# SupergunBasic.net
KiCad netlist of a schematic drawn in EAGLE
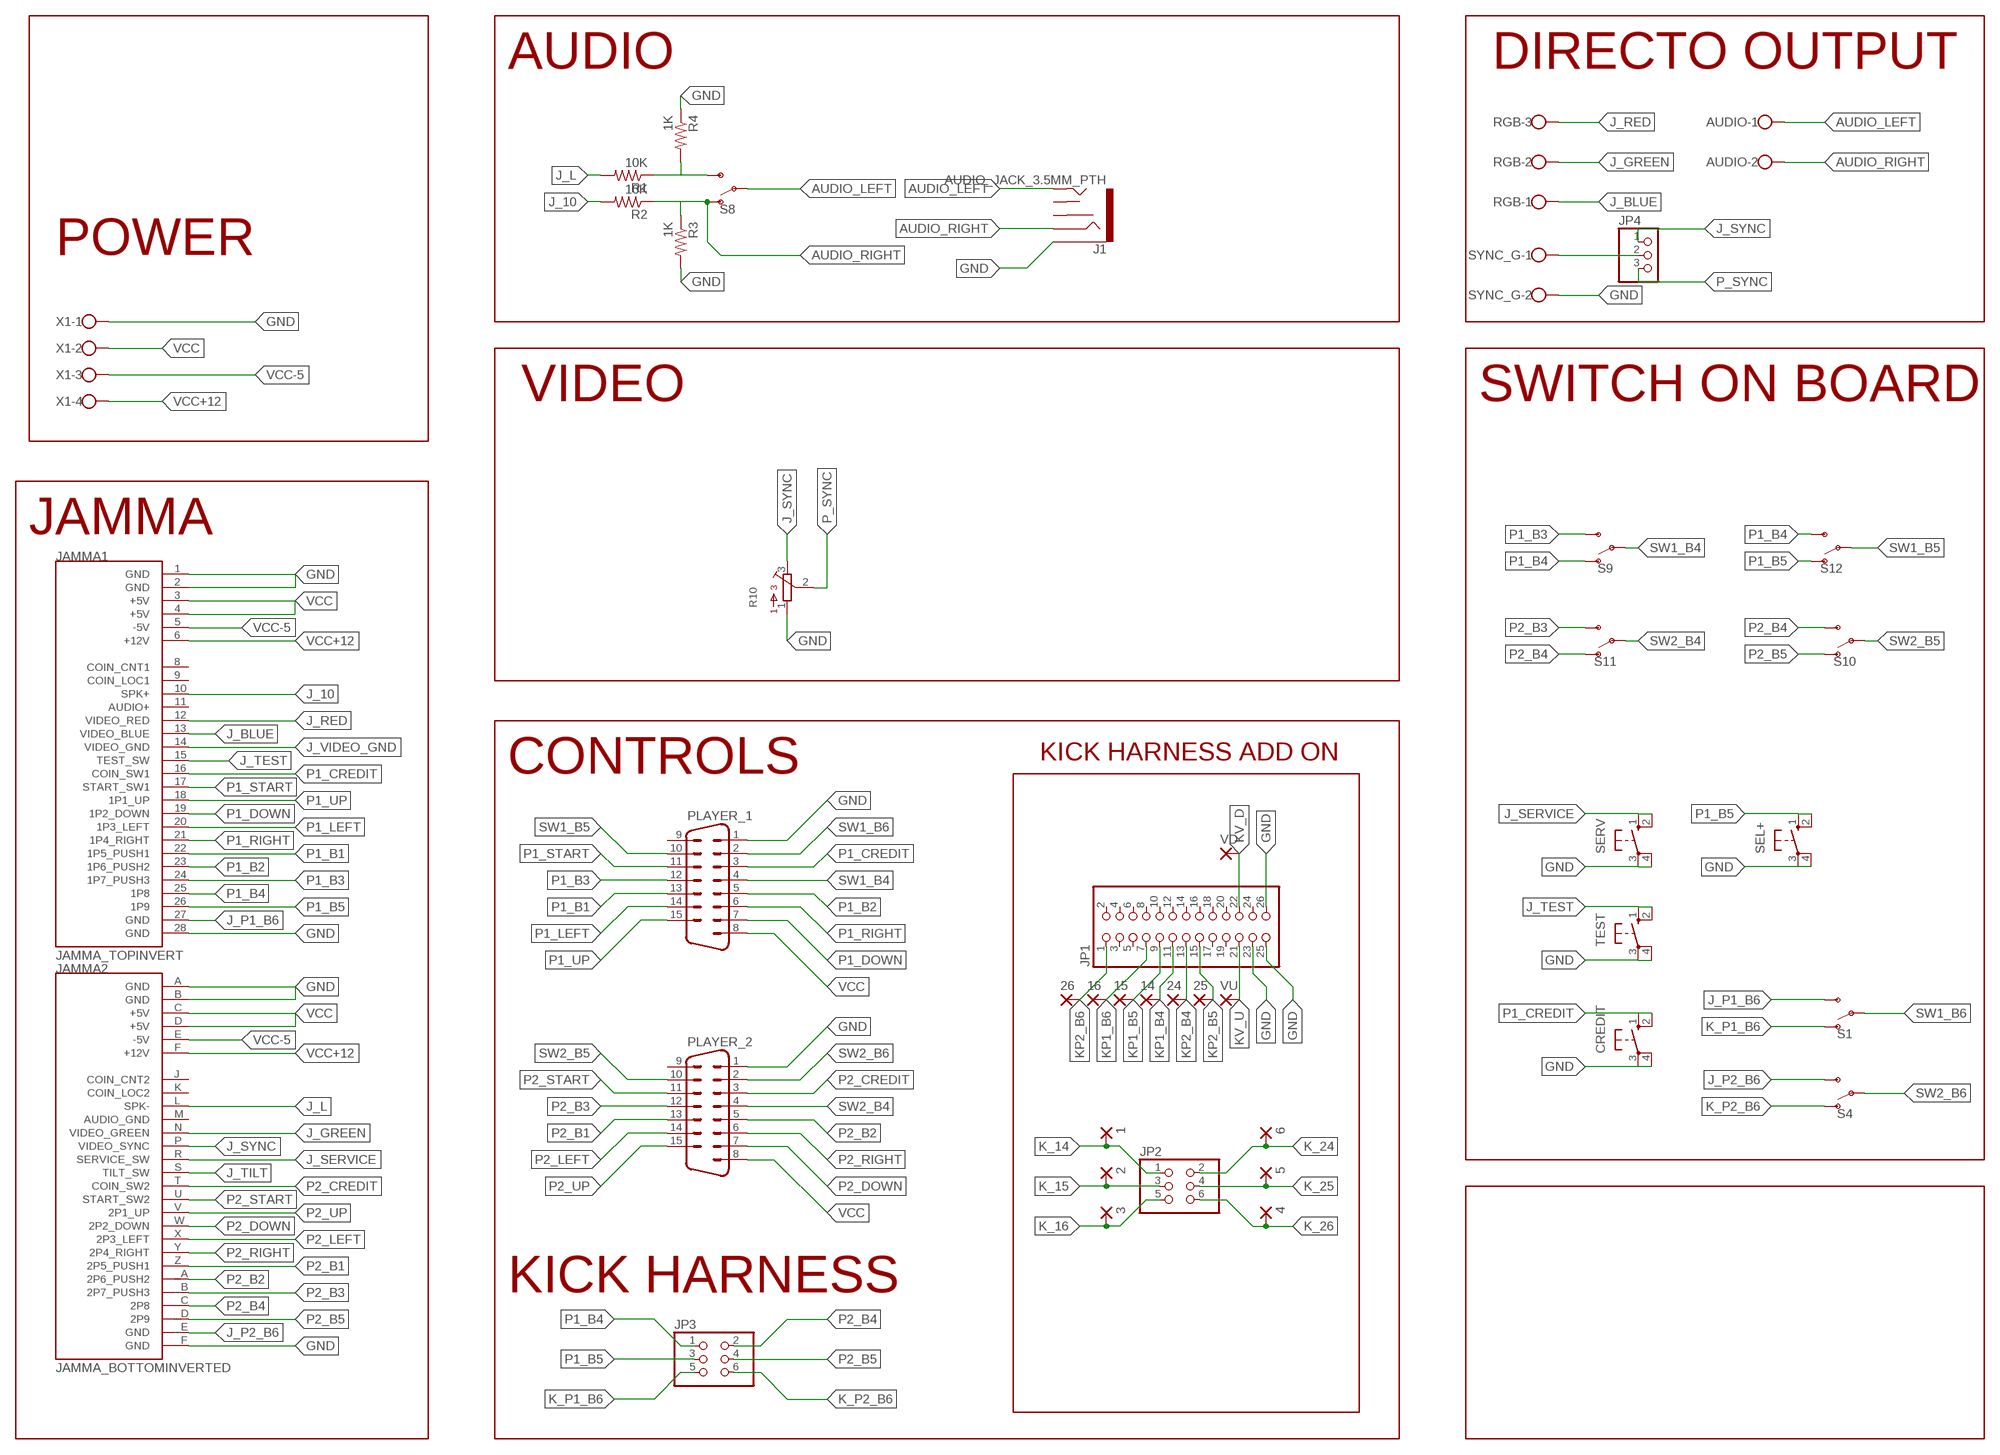
[diagram p0: schematic, sheet 1]

(export (version "E")
  (design (tool "Eeschema 10.0.6"))
  (components
    (comp (ref "1")
      (value "SMD2")
      (footprint "eagle-import:SMD1,27-2,54")
      (libsource (lib "eagle-import") (part "SMD2"))
    )
    (comp (ref "2")
      (value "SMD2")
      (footprint "eagle-import:SMD1,27-2,54")
      (libsource (lib "eagle-import") (part "SMD2"))
    )
    (comp (ref "3")
      (value "SMD2")
      (footprint "eagle-import:SMD1,27-2,54")
      (libsource (lib "eagle-import") (part "SMD2"))
    )
    (comp (ref "4")
      (value "SMD2")
      (footprint "eagle-import:SMD1,27-2,54")
      (libsource (lib "eagle-import") (part "SMD2"))
    )
    (comp (ref "5")
      (value "SMD2")
      (footprint "eagle-import:SMD1,27-2,54")
      (libsource (lib "eagle-import") (part "SMD2"))
    )
    (comp (ref "6")
      (value "SMD2")
      (footprint "eagle-import:SMD1,27-2,54")
      (libsource (lib "eagle-import") (part "SMD2"))
    )
    (comp (ref "14")
      (value "SMD2")
      (footprint "eagle-import:SMD1,27-2,54")
      (libsource (lib "eagle-import") (part "SMD2"))
    )
    (comp (ref "15")
      (value "SMD2")
      (footprint "eagle-import:SMD1,27-2,54")
      (libsource (lib "eagle-import") (part "SMD2"))
    )
    (comp (ref "16")
      (value "SMD2")
      (footprint "eagle-import:SMD1,27-2,54")
      (libsource (lib "eagle-import") (part "SMD2"))
    )
    (comp (ref "24")
      (value "SMD2")
      (footprint "eagle-import:SMD1,27-2,54")
      (libsource (lib "eagle-import") (part "SMD2"))
    )
    (comp (ref "25")
      (value "SMD2")
      (footprint "eagle-import:SMD1,27-2,54")
      (libsource (lib "eagle-import") (part "SMD2"))
    )
    (comp (ref "26")
      (value "SMD2")
      (footprint "eagle-import:SMD1,27-2,54")
      (libsource (lib "eagle-import") (part "SMD2"))
    )
    (comp (ref "AUDIO")
      (value "W237-102")
      (footprint "eagle-import:W237-102")
      (fields (field (name "MPN") "237-102"))
      (libsource (lib "eagle-import") (part "W237-102"))
    )
    (comp (ref "CREDIT")
      (value "10-XX")
      (footprint "eagle-import:B3F-10XX")
      (fields (field (name "MPN") "B3F-1000"))
      (libsource (lib "eagle-import") (part "10-XX"))
    )
    (comp (ref "J1")
      (value "AUDIO_JACK_3.5MM_PTH")
      (footprint "eagle-import:AUDIO-JACK")
      (libsource (lib "eagle-import") (part "AUDIO_JACK_3.5MM_PTH"))
    )
    (comp (ref "JAMMA1")
      (value "JAMMA_TOPINVERT")
      (footprint "eagle-import:JAMMA_TOP_INV")
      (libsource (lib "eagle-import") (part "JAMMA_TOPINVERT"))
    )
    (comp (ref "JAMMA2")
      (value "JAMMA_BOTTOMINVERTED")
      (footprint "eagle-import:JAMMA_BOTTOM_INV")
      (libsource (lib "eagle-import") (part "JAMMA_BOTTOMINVERTED"))
    )
    (comp (ref "JP1")
      (value "PINHD-2X13")
      (footprint "eagle-import:2X13")
      (libsource (lib "eagle-import") (part "PINHD-2X13"))
    )
    (comp (ref "JP2")
      (value "PINHD-2X3")
      (footprint "eagle-import:2X03")
      (libsource (lib "eagle-import") (part "PINHD-2X3"))
    )
    (comp (ref "JP3")
      (value "PINHD-2X3")
      (footprint "eagle-import:2X03")
      (libsource (lib "eagle-import") (part "PINHD-2X3"))
    )
    (comp (ref "JP4")
      (value "PINHD-1X3")
      (footprint "eagle-import:1X03")
      (libsource (lib "eagle-import") (part "PINHD-1X3"))
    )
    (comp (ref "PLAYER_1")
      (value "M15HP")
      (footprint "eagle-import:M15HP")
      (libsource (lib "eagle-import") (part "M15HP"))
    )
    (comp (ref "PLAYER_2")
      (value "M15HP")
      (footprint "eagle-import:M15HP")
      (libsource (lib "eagle-import") (part "M15HP"))
    )
    (comp (ref "R1")
      (value "10K")
      (footprint "eagle-import:0204_7")
      (libsource (lib "eagle-import") (part "R-US_0204/7"))
    )
    (comp (ref "R2")
      (value "10K")
      (footprint "eagle-import:0204_7")
      (libsource (lib "eagle-import") (part "R-US_0204/7"))
    )
    (comp (ref "R3")
      (value "1K")
      (footprint "eagle-import:0204_7")
      (libsource (lib "eagle-import") (part "R-US_0204/7"))
    )
    (comp (ref "R4")
      (value "1K")
      (footprint "eagle-import:0204_7")
      (libsource (lib "eagle-import") (part "R-US_0204/7"))
    )
    (comp (ref "R10")
      (value "3362P")
      (footprint "eagle-import:3362P")
      (libsource (lib "eagle-import") (part "3362P"))
    )
    (comp (ref "RGB")
      (value "W237-103")
      (footprint "eagle-import:W237-103")
      (fields (field (name "MPN") "237-103"))
      (libsource (lib "eagle-import") (part "W237-103"))
    )
    (comp (ref "S1")
      (value "SWITCH-SPDT-PTH-11.6X4.0MM")
      (footprint "eagle-import:SWITCH_SPDT_PTH_11.6X4.0MM")
      (libsource (lib "eagle-import") (part "SWITCH-SPDT-PTH-11.6X4.0MM"))
    )
    (comp (ref "S4")
      (value "SWITCH-SPDT-PTH-11.6X4.0MM")
      (footprint "eagle-import:SWITCH_SPDT_PTH_11.6X4.0MM")
      (libsource (lib "eagle-import") (part "SWITCH-SPDT-PTH-11.6X4.0MM"))
    )
    (comp (ref "S8")
      (value "SWITCH-SPDT-PTH-11.6X4.0MM")
      (footprint "eagle-import:SWITCH_SPDT_PTH_11.6X4.0MM")
      (libsource (lib "eagle-import") (part "SWITCH-SPDT-PTH-11.6X4.0MM"))
    )
    (comp (ref "S9")
      (value "SWITCH-SPDT-PTH-11.6X4.0MM")
      (footprint "eagle-import:SWITCH_SPDT_PTH_11.6X4.0MM")
      (libsource (lib "eagle-import") (part "SWITCH-SPDT-PTH-11.6X4.0MM"))
    )
    (comp (ref "S10")
      (value "SWITCH-SPDT-PTH-11.6X4.0MM")
      (footprint "eagle-import:SWITCH_SPDT_PTH_11.6X4.0MM")
      (libsource (lib "eagle-import") (part "SWITCH-SPDT-PTH-11.6X4.0MM"))
    )
    (comp (ref "S11")
      (value "SWITCH-SPDT-PTH-11.6X4.0MM")
      (footprint "eagle-import:SWITCH_SPDT_PTH_11.6X4.0MM")
      (libsource (lib "eagle-import") (part "SWITCH-SPDT-PTH-11.6X4.0MM"))
    )
    (comp (ref "S12")
      (value "SWITCH-SPDT-PTH-11.6X4.0MM")
      (footprint "eagle-import:SWITCH_SPDT_PTH_11.6X4.0MM")
      (libsource (lib "eagle-import") (part "SWITCH-SPDT-PTH-11.6X4.0MM"))
    )
    (comp (ref "SEL+")
      (value "10-XX")
      (footprint "eagle-import:B3F-10XX")
      (fields (field (name "MPN") "B3F-1000"))
      (libsource (lib "eagle-import") (part "10-XX"))
    )
    (comp (ref "SERV")
      (value "10-XX")
      (footprint "eagle-import:B3F-10XX")
      (fields (field (name "MPN") "B3F-1000"))
      (libsource (lib "eagle-import") (part "10-XX"))
    )
    (comp (ref "SYNC_G")
      (value "W237-102")
      (footprint "eagle-import:W237-102")
      (fields (field (name "MPN") "237-102"))
      (libsource (lib "eagle-import") (part "W237-102"))
    )
    (comp (ref "TEST")
      (value "10-XX")
      (footprint "eagle-import:B3F-10XX")
      (fields (field (name "MPN") "B3F-1000"))
      (libsource (lib "eagle-import") (part "10-XX"))
    )
    (comp (ref "VD")
      (value "SMD2")
      (footprint "eagle-import:SMD1,27-2,54")
      (libsource (lib "eagle-import") (part "SMD2"))
    )
    (comp (ref "VU")
      (value "SMD2")
      (footprint "eagle-import:SMD1,27-2,54")
      (libsource (lib "eagle-import") (part "SMD2"))
    )
    (comp (ref "X1")
      (value "W237-4")
      (footprint "eagle-import:W237-4")
      (libsource (lib "eagle-import") (part "W237-4"))
    )
  )
  (nets
    (net (code "1") (name "AUDIO_LEFT") (class "Default")
      (node (ref "AUDIO") (pin "1") (pinfunction "KL_1") (pintype "passive"))
      (node (ref "J1") (pin "TIP") (pinfunction "TIP_TIP") (pintype "bidirectional"))
      (node (ref "S8") (pin "2") (pinfunction "P_2") (pintype "passive"))
    )
    (net (code "2") (name "AUDIO_RIGHT") (class "Default")
      (node (ref "AUDIO") (pin "2") (pinfunction "KL_2") (pintype "passive"))
      (node (ref "J1") (pin "RING") (pinfunction "RING_RING") (pintype "bidirectional"))
      (node (ref "R2") (pin "1") (pinfunction "1_1") (pintype "passive"))
      (node (ref "R3") (pin "1") (pinfunction "1_1") (pintype "passive"))
      (node (ref "S8") (pin "1") (pinfunction "O_1") (pintype "passive"))
    )
    (net (code "3") (name "GND") (class "Default")
      (node (ref "CREDIT") (pin "3") (pinfunction "P_3") (pintype "passive"))
      (node (ref "CREDIT") (pin "4") (pinfunction "P1_4") (pintype "passive"))
      (node (ref "J1") (pin "SLEEVE") (pinfunction "SLEEVE_SLEEVE") (pintype "bidirectional"))
      (node (ref "JAMMA1") (pin "1") (pinfunction "GND_1") (pintype "power_in"))
      (node (ref "JAMMA1") (pin "2") (pinfunction "GND_2") (pintype "power_in"))
      (node (ref "JAMMA1") (pin "28") (pinfunction "GND_28") (pintype "power_in"))
      (node (ref "JAMMA2") (pin "A") (pinfunction "GND_A") (pintype "power_in"))
      (node (ref "JAMMA2") (pin "B") (pinfunction "GND_B") (pintype "power_in"))
      (node (ref "JAMMA2") (pin "_F") (pinfunction "GND__F") (pintype "power_in"))
      (node (ref "JP1") (pin "23") (pinfunction "23_23") (pintype "passive"))
      (node (ref "JP1") (pin "25") (pinfunction "25_25") (pintype "passive"))
      (node (ref "JP1") (pin "26") (pinfunction "26_26") (pintype "passive"))
      (node (ref "PLAYER_1") (pin "1") (pinfunction "1_1") (pintype "passive"))
      (node (ref "PLAYER_2") (pin "1") (pinfunction "1_1") (pintype "passive"))
      (node (ref "R10") (pin "1") (pinfunction "1_1") (pintype "passive"))
      (node (ref "R3") (pin "2") (pinfunction "2_2") (pintype "passive"))
      (node (ref "R4") (pin "1") (pinfunction "1_1") (pintype "passive"))
      (node (ref "SEL+") (pin "3") (pinfunction "P_3") (pintype "passive"))
      (node (ref "SEL+") (pin "4") (pinfunction "P1_4") (pintype "passive"))
      (node (ref "SERV") (pin "3") (pinfunction "P_3") (pintype "passive"))
      (node (ref "SERV") (pin "4") (pinfunction "P1_4") (pintype "passive"))
      (node (ref "SYNC_G") (pin "2") (pinfunction "KL_2") (pintype "passive"))
      (node (ref "TEST") (pin "3") (pinfunction "P_3") (pintype "passive"))
      (node (ref "TEST") (pin "4") (pinfunction "P1_4") (pintype "passive"))
      (node (ref "X1") (pin "1") (pinfunction "KL_1") (pintype "passive"))
    )
    (net (code "4") (name "J_10") (class "Default")
      (node (ref "JAMMA1") (pin "10") (pinfunction "SPK+_10") (pintype "output"))
      (node (ref "R2") (pin "2") (pinfunction "2_2") (pintype "passive"))
    )
    (net (code "5") (name "J_BLUE") (class "Default")
      (node (ref "JAMMA1") (pin "13") (pinfunction "VIDEO_BLUE_13") (pintype "output"))
      (node (ref "RGB") (pin "1") (pinfunction "KL_1") (pintype "passive"))
    )
    (net (code "6") (name "J_GREEN") (class "Default")
      (node (ref "JAMMA2") (pin "N") (pinfunction "VIDEO_GREEN_N") (pintype "output"))
      (node (ref "RGB") (pin "2") (pinfunction "KL_2") (pintype "passive"))
    )
    (net (code "7") (name "J_L") (class "Default")
      (node (ref "JAMMA2") (pin "L") (pinfunction "SPK-_L") (pintype "output"))
      (node (ref "R1") (pin "2") (pinfunction "2_2") (pintype "passive"))
    )
    (net (code "8") (name "J_P1_B6") (class "Default")
      (node (ref "JAMMA1") (pin "27") (pinfunction "GND_27") (pintype "power_in"))
      (node (ref "S1") (pin "3") (pinfunction "S_3") (pintype "passive"))
    )
    (net (code "9") (name "J_P2_B6") (class "Default")
      (node (ref "JAMMA2") (pin "_E") (pinfunction "GND__E") (pintype "power_in"))
      (node (ref "S4") (pin "3") (pinfunction "S_3") (pintype "passive"))
    )
    (net (code "10") (name "J_RED") (class "Default")
      (node (ref "JAMMA1") (pin "12") (pinfunction "VIDEO_RED_12") (pintype "output"))
      (node (ref "RGB") (pin "3") (pinfunction "KL_3") (pintype "passive"))
    )
    (net (code "11") (name "J_SERVICE") (class "Default")
      (node (ref "JAMMA2") (pin "R") (pinfunction "SERVICE_SW_R") (pintype "input"))
      (node (ref "SERV") (pin "1") (pinfunction "S_1") (pintype "passive"))
      (node (ref "SERV") (pin "2") (pinfunction "S1_2") (pintype "passive"))
    )
    (net (code "12") (name "J_SYNC") (class "Default")
      (node (ref "JAMMA2") (pin "P") (pinfunction "VIDEO_SYNC_P") (pintype "output"))
      (node (ref "JP4") (pin "1") (pinfunction "1_1") (pintype "passive"))
      (node (ref "R10") (pin "3") (pinfunction "3_3") (pintype "passive"))
    )
    (net (code "13") (name "J_TEST") (class "Default")
      (node (ref "JAMMA1") (pin "15") (pinfunction "TEST_SW_15") (pintype "input"))
      (node (ref "TEST") (pin "1") (pinfunction "S_1") (pintype "passive"))
      (node (ref "TEST") (pin "2") (pinfunction "S1_2") (pintype "passive"))
    )
    (net (code "14") (name "J_TILT") (class "Default")
      (node (ref "JAMMA2") (pin "S") (pinfunction "TILT_SW_S") (pintype "input"))
    )
    (net (code "15") (name "J_VIDEO_GND") (class "Default")
      (node (ref "JAMMA1") (pin "14") (pinfunction "VIDEO_GND_14") (pintype "output"))
    )
    (net (code "16") (name "KP1_B4") (class "Default")
      (node (ref "14") (pin "1") (pinfunction "P_1") (pintype "passive"))
      (node (ref "JP1") (pin "11") (pinfunction "11_11") (pintype "passive"))
    )
    (net (code "17") (name "KP1_B5") (class "Default")
      (node (ref "15") (pin "1") (pinfunction "P_1") (pintype "passive"))
      (node (ref "JP1") (pin "9") (pinfunction "9_9") (pintype "passive"))
    )
    (net (code "18") (name "KP1_B6") (class "Default")
      (node (ref "16") (pin "1") (pinfunction "P_1") (pintype "passive"))
      (node (ref "JP1") (pin "7") (pinfunction "7_7") (pintype "passive"))
    )
    (net (code "19") (name "KP2_B4") (class "Default")
      (node (ref "24") (pin "1") (pinfunction "P_1") (pintype "passive"))
      (node (ref "JP1") (pin "13") (pinfunction "13_13") (pintype "passive"))
    )
    (net (code "20") (name "KP2_B5") (class "Default")
      (node (ref "25") (pin "1") (pinfunction "P_1") (pintype "passive"))
      (node (ref "JP1") (pin "15") (pinfunction "15_15") (pintype "passive"))
    )
    (net (code "21") (name "KP2_B6") (class "Default")
      (node (ref "26") (pin "1") (pinfunction "P_1") (pintype "passive"))
      (node (ref "JP1") (pin "1") (pinfunction "1_1") (pintype "passive"))
    )
    (net (code "22") (name "KV_D") (class "Default")
      (node (ref "JP1") (pin "22") (pinfunction "22_22") (pintype "passive"))
      (node (ref "VD") (pin "1") (pinfunction "P_1") (pintype "passive"))
    )
    (net (code "23") (name "KV_U") (class "Default")
      (node (ref "JP1") (pin "21") (pinfunction "21_21") (pintype "passive"))
      (node (ref "VU") (pin "1") (pinfunction "P_1") (pintype "passive"))
    )
    (net (code "24") (name "K_14") (class "Default")
      (node (ref "1") (pin "1") (pinfunction "P_1") (pintype "passive"))
      (node (ref "JP2") (pin "1") (pinfunction "1_1") (pintype "passive"))
    )
    (net (code "25") (name "K_15") (class "Default")
      (node (ref "2") (pin "1") (pinfunction "P_1") (pintype "passive"))
      (node (ref "JP2") (pin "3") (pinfunction "3_3") (pintype "passive"))
    )
    (net (code "26") (name "K_16") (class "Default")
      (node (ref "3") (pin "1") (pinfunction "P_1") (pintype "passive"))
      (node (ref "JP2") (pin "5") (pinfunction "5_5") (pintype "passive"))
    )
    (net (code "27") (name "K_24") (class "Default")
      (node (ref "6") (pin "1") (pinfunction "P_1") (pintype "passive"))
      (node (ref "JP2") (pin "2") (pinfunction "2_2") (pintype "passive"))
    )
    (net (code "28") (name "K_25") (class "Default")
      (node (ref "5") (pin "1") (pinfunction "P_1") (pintype "passive"))
      (node (ref "JP2") (pin "4") (pinfunction "4_4") (pintype "passive"))
    )
    (net (code "29") (name "K_26") (class "Default")
      (node (ref "4") (pin "1") (pinfunction "P_1") (pintype "passive"))
      (node (ref "JP2") (pin "6") (pinfunction "6_6") (pintype "passive"))
    )
    (net (code "30") (name "K_P1_B6") (class "Default")
      (node (ref "JP3") (pin "5") (pinfunction "5_5") (pintype "passive"))
      (node (ref "S1") (pin "1") (pinfunction "O_1") (pintype "passive"))
    )
    (net (code "31") (name "K_P2_B6") (class "Default")
      (node (ref "JP3") (pin "6") (pinfunction "6_6") (pintype "passive"))
      (node (ref "S4") (pin "1") (pinfunction "O_1") (pintype "passive"))
    )
    (net (code "32") (name "Net-(S8-S)") (class "Default")
      (node (ref "R1") (pin "1") (pinfunction "1_1") (pintype "passive"))
      (node (ref "R4") (pin "2") (pinfunction "2_2") (pintype "passive"))
      (node (ref "S8") (pin "3") (pinfunction "S_3") (pintype "passive"))
    )
    (net (code "33") (name "Net-(SYNC_GA-KL)") (class "Default")
      (node (ref "JP4") (pin "2") (pinfunction "2_2") (pintype "passive"))
      (node (ref "SYNC_G") (pin "1") (pinfunction "KL_1") (pintype "passive"))
    )
    (net (code "34") (name "P1_B1") (class "Default")
      (node (ref "JAMMA1") (pin "22") (pinfunction "1P5_PUSH1_22") (pintype "input"))
      (node (ref "PLAYER_1") (pin "13") (pinfunction "13_13") (pintype "passive"))
    )
    (net (code "35") (name "P1_B2") (class "Default")
      (node (ref "JAMMA1") (pin "23") (pinfunction "1P6_PUSH2_23") (pintype "input"))
      (node (ref "PLAYER_1") (pin "5") (pinfunction "5_5") (pintype "passive"))
    )
    (net (code "36") (name "P1_B3") (class "Default")
      (node (ref "JAMMA1") (pin "24") (pinfunction "1P7_PUSH3_24") (pintype "input"))
      (node (ref "PLAYER_1") (pin "12") (pinfunction "12_12") (pintype "passive"))
      (node (ref "S9") (pin "3") (pinfunction "S_3") (pintype "passive"))
    )
    (net (code "37") (name "P1_B4") (class "Default")
      (node (ref "JAMMA1") (pin "25") (pinfunction "1P8_25") (pintype "input"))
      (node (ref "JP3") (pin "1") (pinfunction "1_1") (pintype "passive"))
      (node (ref "S12") (pin "3") (pinfunction "S_3") (pintype "passive"))
      (node (ref "S9") (pin "1") (pinfunction "O_1") (pintype "passive"))
    )
    (net (code "38") (name "P1_B5") (class "Default")
      (node (ref "JAMMA1") (pin "26") (pinfunction "1P9_26") (pintype "input"))
      (node (ref "JP3") (pin "3") (pinfunction "3_3") (pintype "passive"))
      (node (ref "S12") (pin "1") (pinfunction "O_1") (pintype "passive"))
      (node (ref "SEL+") (pin "1") (pinfunction "S_1") (pintype "passive"))
      (node (ref "SEL+") (pin "2") (pinfunction "S1_2") (pintype "passive"))
    )
    (net (code "39") (name "P1_CREDIT") (class "Default")
      (node (ref "CREDIT") (pin "1") (pinfunction "S_1") (pintype "passive"))
      (node (ref "CREDIT") (pin "2") (pinfunction "S1_2") (pintype "passive"))
      (node (ref "JAMMA1") (pin "16") (pinfunction "COIN_SW1_16") (pintype "input"))
      (node (ref "PLAYER_1") (pin "3") (pinfunction "3_3") (pintype "passive"))
    )
    (net (code "40") (name "P1_DOWN") (class "Default")
      (node (ref "JAMMA1") (pin "19") (pinfunction "1P2_DOWN_19") (pintype "input"))
      (node (ref "PLAYER_1") (pin "7") (pinfunction "7_7") (pintype "passive"))
    )
    (net (code "41") (name "P1_LEFT") (class "Default")
      (node (ref "JAMMA1") (pin "20") (pinfunction "1P3_LEFT_20") (pintype "input"))
      (node (ref "PLAYER_1") (pin "14") (pinfunction "14_14") (pintype "passive"))
    )
    (net (code "42") (name "P1_RIGHT") (class "Default")
      (node (ref "JAMMA1") (pin "21") (pinfunction "1P4_RIGHT_21") (pintype "input"))
      (node (ref "PLAYER_1") (pin "6") (pinfunction "6_6") (pintype "passive"))
    )
    (net (code "43") (name "P1_START") (class "Default")
      (node (ref "JAMMA1") (pin "17") (pinfunction "START_SW1_17") (pintype "input"))
      (node (ref "PLAYER_1") (pin "11") (pinfunction "11_11") (pintype "passive"))
    )
    (net (code "44") (name "P1_UP") (class "Default")
      (node (ref "JAMMA1") (pin "18") (pinfunction "1P1_UP_18") (pintype "input"))
      (node (ref "PLAYER_1") (pin "15") (pinfunction "15_15") (pintype "passive"))
    )
    (net (code "45") (name "P2_B1") (class "Default")
      (node (ref "JAMMA2") (pin "Z") (pinfunction "2P5_PUSH1_Z") (pintype "input"))
      (node (ref "PLAYER_2") (pin "13") (pinfunction "13_13") (pintype "passive"))
    )
    (net (code "46") (name "P2_B2") (class "Default")
      (node (ref "JAMMA2") (pin "_A") (pinfunction "2P6_PUSH2__A") (pintype "input"))
      (node (ref "PLAYER_2") (pin "5") (pinfunction "5_5") (pintype "passive"))
    )
    (net (code "47") (name "P2_B3") (class "Default")
      (node (ref "JAMMA2") (pin "_B") (pinfunction "2P7_PUSH3__B") (pintype "input"))
      (node (ref "PLAYER_2") (pin "12") (pinfunction "12_12") (pintype "passive"))
      (node (ref "S11") (pin "3") (pinfunction "S_3") (pintype "passive"))
    )
    (net (code "48") (name "P2_B4") (class "Default")
      (node (ref "JAMMA2") (pin "_C") (pinfunction "2P8__C") (pintype "input"))
      (node (ref "JP3") (pin "2") (pinfunction "2_2") (pintype "passive"))
      (node (ref "S10") (pin "3") (pinfunction "S_3") (pintype "passive"))
      (node (ref "S11") (pin "1") (pinfunction "O_1") (pintype "passive"))
    )
    (net (code "49") (name "P2_B5") (class "Default")
      (node (ref "JAMMA2") (pin "_D") (pinfunction "2P9__D") (pintype "input"))
      (node (ref "JP3") (pin "4") (pinfunction "4_4") (pintype "passive"))
      (node (ref "S10") (pin "1") (pinfunction "O_1") (pintype "passive"))
    )
    (net (code "50") (name "P2_CREDIT") (class "Default")
      (node (ref "JAMMA2") (pin "T") (pinfunction "COIN_SW2_T") (pintype "input"))
      (node (ref "PLAYER_2") (pin "3") (pinfunction "3_3") (pintype "passive"))
    )
    (net (code "51") (name "P2_DOWN") (class "Default")
      (node (ref "JAMMA2") (pin "W") (pinfunction "2P2_DOWN_W") (pintype "input"))
      (node (ref "PLAYER_2") (pin "7") (pinfunction "7_7") (pintype "passive"))
    )
    (net (code "52") (name "P2_LEFT") (class "Default")
      (node (ref "JAMMA2") (pin "X") (pinfunction "2P3_LEFT_X") (pintype "input"))
      (node (ref "PLAYER_2") (pin "14") (pinfunction "14_14") (pintype "passive"))
    )
    (net (code "53") (name "P2_RIGHT") (class "Default")
      (node (ref "JAMMA2") (pin "Y") (pinfunction "2P4_RIGHT_Y") (pintype "input"))
      (node (ref "PLAYER_2") (pin "6") (pinfunction "6_6") (pintype "passive"))
    )
    (net (code "54") (name "P2_START") (class "Default")
      (node (ref "JAMMA2") (pin "U") (pinfunction "START_SW2_U") (pintype "input"))
      (node (ref "PLAYER_2") (pin "11") (pinfunction "11_11") (pintype "passive"))
    )
    (net (code "55") (name "P2_UP") (class "Default")
      (node (ref "JAMMA2") (pin "V") (pinfunction "2P1_UP_V") (pintype "input"))
      (node (ref "PLAYER_2") (pin "15") (pinfunction "15_15") (pintype "passive"))
    )
    (net (code "56") (name "P_SYNC") (class "Default")
      (node (ref "JP4") (pin "3") (pinfunction "3_3") (pintype "passive"))
      (node (ref "R10") (pin "2") (pinfunction "2_2") (pintype "passive"))
    )
    (net (code "57") (name "SW1_B4") (class "Default")
      (node (ref "PLAYER_1") (pin "4") (pinfunction "4_4") (pintype "passive"))
      (node (ref "S9") (pin "2") (pinfunction "P_2") (pintype "passive"))
    )
    (net (code "58") (name "SW1_B5") (class "Default")
      (node (ref "PLAYER_1") (pin "10") (pinfunction "10_10") (pintype "passive"))
      (node (ref "S12") (pin "2") (pinfunction "P_2") (pintype "passive"))
    )
    (net (code "59") (name "SW1_B6") (class "Default")
      (node (ref "PLAYER_1") (pin "2") (pinfunction "2_2") (pintype "passive"))
      (node (ref "S1") (pin "2") (pinfunction "P_2") (pintype "passive"))
    )
    (net (code "60") (name "SW2_B4") (class "Default")
      (node (ref "PLAYER_2") (pin "4") (pinfunction "4_4") (pintype "passive"))
      (node (ref "S11") (pin "2") (pinfunction "P_2") (pintype "passive"))
    )
    (net (code "61") (name "SW2_B5") (class "Default")
      (node (ref "PLAYER_2") (pin "10") (pinfunction "10_10") (pintype "passive"))
      (node (ref "S10") (pin "2") (pinfunction "P_2") (pintype "passive"))
    )
    (net (code "62") (name "SW2_B6") (class "Default")
      (node (ref "PLAYER_2") (pin "2") (pinfunction "2_2") (pintype "passive"))
      (node (ref "S4") (pin "2") (pinfunction "P_2") (pintype "passive"))
    )
    (net (code "63") (name "VCC") (class "Default")
      (node (ref "JAMMA1") (pin "3") (pinfunction "+5V_3") (pintype "power_in"))
      (node (ref "JAMMA1") (pin "4") (pinfunction "+5V_4") (pintype "power_in"))
      (node (ref "JAMMA2") (pin "C") (pinfunction "+5V_C") (pintype "power_in"))
      (node (ref "JAMMA2") (pin "D") (pinfunction "+5V_D") (pintype "power_in"))
      (node (ref "PLAYER_1") (pin "8") (pinfunction "8_8") (pintype "passive"))
      (node (ref "PLAYER_2") (pin "8") (pinfunction "8_8") (pintype "passive"))
      (node (ref "X1") (pin "2") (pinfunction "KL_2") (pintype "passive"))
    )
    (net (code "64") (name "VCC+12") (class "Default")
      (node (ref "JAMMA1") (pin "6") (pinfunction "+12V_6") (pintype "power_in"))
      (node (ref "JAMMA2") (pin "F") (pinfunction "+12V_F") (pintype "power_in"))
      (node (ref "X1") (pin "4") (pinfunction "KL_4") (pintype "passive"))
    )
    (net (code "65") (name "VCC-5") (class "Default")
      (node (ref "JAMMA1") (pin "5") (pinfunction "-5V_5") (pintype "power_in"))
      (node (ref "JAMMA2") (pin "E") (pinfunction "-5V_E") (pintype "power_in"))
      (node (ref "X1") (pin "3") (pinfunction "KL_3") (pintype "passive"))
    )
    (net (code "66") (name "unconnected-(J1-PadRSH)") (class "Default")
      (node (ref "J1") (pin "RSH") (pinfunction "RSH_RSH") (pintype "bidirectional"))
    )
    (net (code "67") (name "unconnected-(J1-PadTSH)") (class "Default")
      (node (ref "J1") (pin "TSH") (pinfunction "TSH_TSH") (pintype "bidirectional"))
    )
    (net (code "68") (name "unconnected-(JAMMA1-AUDIO+-Pad11)") (class "Default")
      (node (ref "JAMMA1") (pin "11") (pinfunction "AUDIO+_11") (pintype "output"))
    )
    (net (code "69") (name "unconnected-(JAMMA1-COIN_CNT1-Pad8)") (class "Default")
      (node (ref "JAMMA1") (pin "8") (pinfunction "COIN_CNT1_8") (pintype "output"))
    )
    (net (code "70") (name "unconnected-(JAMMA1-COIN_LOC1-Pad9)") (class "Default")
      (node (ref "JAMMA1") (pin "9") (pinfunction "COIN_LOC1_9") (pintype "output"))
    )
    (net (code "71") (name "unconnected-(JAMMA2-AUDIO_GND-PadM)") (class "Default")
      (node (ref "JAMMA2") (pin "M") (pinfunction "AUDIO_GND_M") (pintype "output"))
    )
    (net (code "72") (name "unconnected-(JAMMA2-COIN_CNT2-PadJ)") (class "Default")
      (node (ref "JAMMA2") (pin "J") (pinfunction "COIN_CNT2_J") (pintype "output"))
    )
    (net (code "73") (name "unconnected-(JAMMA2-COIN_LOC2-PadK)") (class "Default")
      (node (ref "JAMMA2") (pin "K") (pinfunction "COIN_LOC2_K") (pintype "output"))
    )
    (net (code "74") (name "unconnected-(JP1-Pad2)") (class "Default")
      (node (ref "JP1") (pin "2") (pinfunction "2_2") (pintype "passive"))
    )
    (net (code "75") (name "unconnected-(JP1-Pad3)") (class "Default")
      (node (ref "JP1") (pin "3") (pinfunction "3_3") (pintype "passive"))
    )
    (net (code "76") (name "unconnected-(JP1-Pad4)") (class "Default")
      (node (ref "JP1") (pin "4") (pinfunction "4_4") (pintype "passive"))
    )
    (net (code "77") (name "unconnected-(JP1-Pad5)") (class "Default")
      (node (ref "JP1") (pin "5") (pinfunction "5_5") (pintype "passive"))
    )
    (net (code "78") (name "unconnected-(JP1-Pad6)") (class "Default")
      (node (ref "JP1") (pin "6") (pinfunction "6_6") (pintype "passive"))
    )
    (net (code "79") (name "unconnected-(JP1-Pad8)") (class "Default")
      (node (ref "JP1") (pin "8") (pinfunction "8_8") (pintype "passive"))
    )
    (net (code "80") (name "unconnected-(JP1-Pad10)") (class "Default")
      (node (ref "JP1") (pin "10") (pinfunction "10_10") (pintype "passive"))
    )
    (net (code "81") (name "unconnected-(JP1-Pad12)") (class "Default")
      (node (ref "JP1") (pin "12") (pinfunction "12_12") (pintype "passive"))
    )
    (net (code "82") (name "unconnected-(JP1-Pad14)") (class "Default")
      (node (ref "JP1") (pin "14") (pinfunction "14_14") (pintype "passive"))
    )
    (net (code "83") (name "unconnected-(JP1-Pad16)") (class "Default")
      (node (ref "JP1") (pin "16") (pinfunction "16_16") (pintype "passive"))
    )
    (net (code "84") (name "unconnected-(JP1-Pad17)") (class "Default")
      (node (ref "JP1") (pin "17") (pinfunction "17_17") (pintype "passive"))
    )
    (net (code "85") (name "unconnected-(JP1-Pad18)") (class "Default")
      (node (ref "JP1") (pin "18") (pinfunction "18_18") (pintype "passive"))
    )
    (net (code "86") (name "unconnected-(JP1-Pad19)") (class "Default")
      (node (ref "JP1") (pin "19") (pinfunction "19_19") (pintype "passive"))
    )
    (net (code "87") (name "unconnected-(JP1-Pad20)") (class "Default")
      (node (ref "JP1") (pin "20") (pinfunction "20_20") (pintype "passive"))
    )
    (net (code "88") (name "unconnected-(JP1-Pad24)") (class "Default")
      (node (ref "JP1") (pin "24") (pinfunction "24_24") (pintype "passive"))
    )
    (net (code "89") (name "unconnected-(PLAYER_1-Pad9)") (class "Default")
      (node (ref "PLAYER_1") (pin "9") (pinfunction "9_9") (pintype "passive"))
    )
    (net (code "90") (name "unconnected-(PLAYER_2-Pad9)") (class "Default")
      (node (ref "PLAYER_2") (pin "9") (pinfunction "9_9") (pintype "passive"))
    )
  )
)
